# Sheet1.net
KiCad netlist of a schematic drawn in Altium Designer
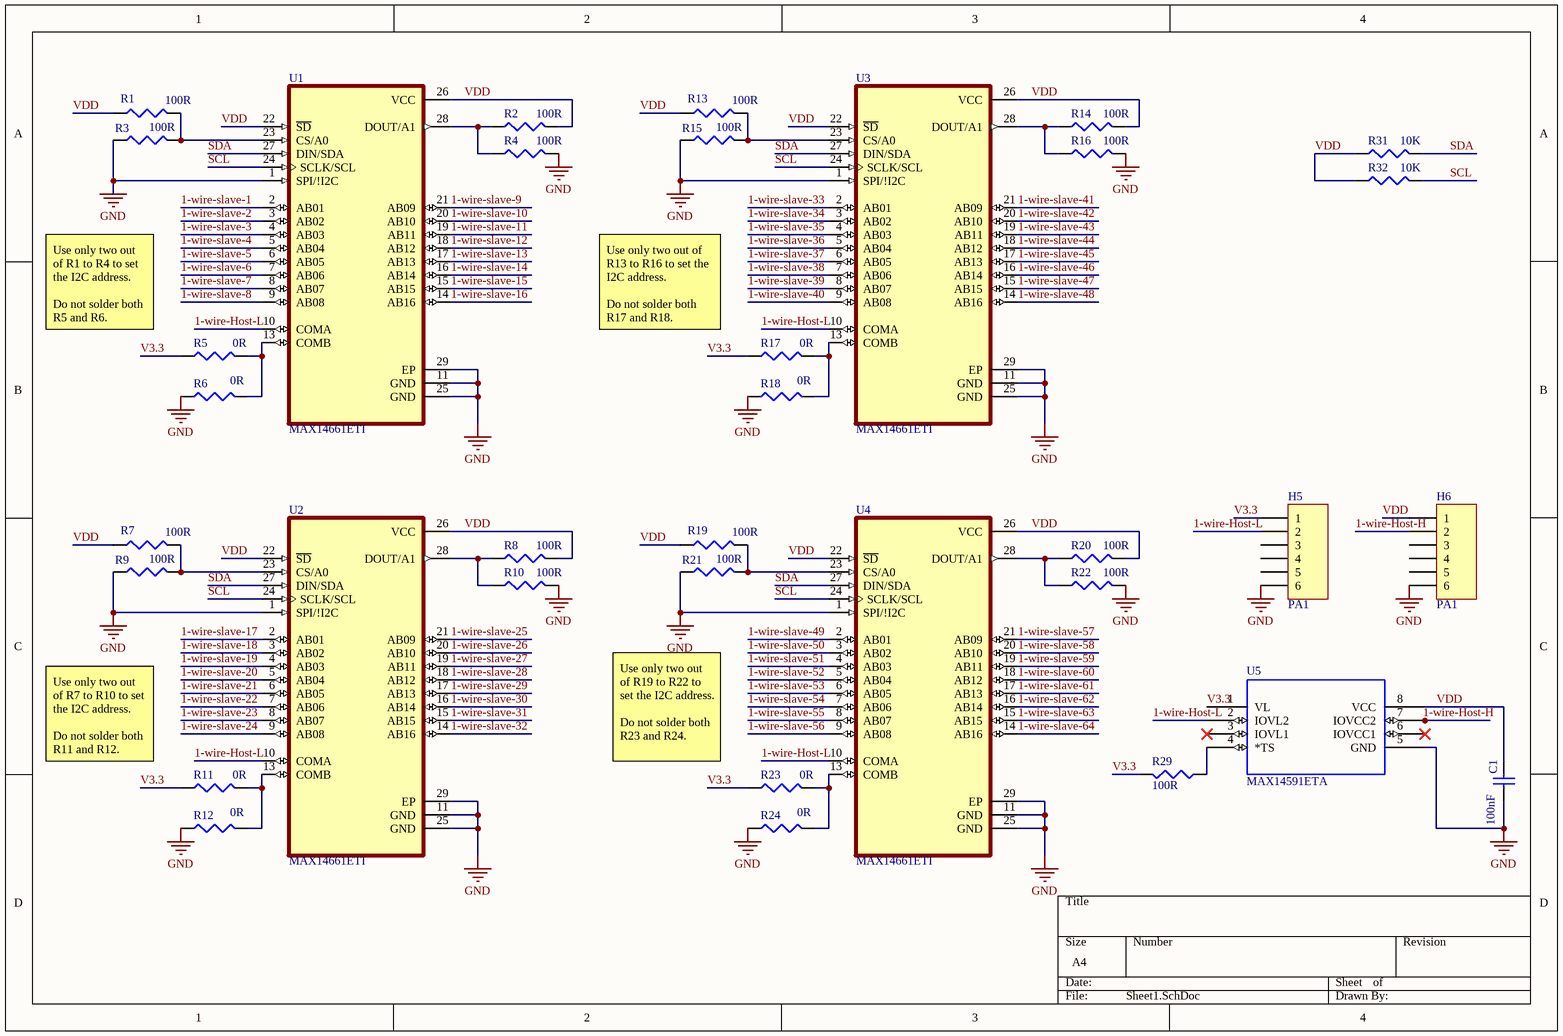
[diagram p0: Sheet1.SchDoc]

(export (version "E")
  (design (tool "Eeschema 10.0.6"))
  (components
    (comp (ref "C1")
      (value "100nF")
      (footprint "CAPC1608L")
      (description "Capacitor (Semiconductor SIM Model)")
      (fields (field (name "PUBLISHER") "Altium Limited"))
      (libsource (lib "Miscellaneous Devices") (part "Cap Semi"))
    )
    (comp (ref "H5")
      (value "PA1")
      (footprint "HDR1X6")
      (description "Header, 6-Pin")
      (fields (field (name "PUBLISHER") "Altium Limited"))
      (libsource (lib "Miscellaneous Connectors") (part "Header 6"))
    )
    (comp (ref "H6")
      (value "PA1")
      (footprint "HDR1X6")
      (description "Header, 6-Pin")
      (fields (field (name "PUBLISHER") "Altium Limited"))
      (libsource (lib "Miscellaneous Connectors") (part "Header 6"))
    )
    (comp (ref "R1")
      (value "100R")
      (footprint "J1-0603")
      (description "Resistor")
      (fields (field (name "PUBLISHER") "Altium Limited"))
      (libsource (lib "Miscellaneous Devices") (part "Res3"))
    )
    (comp (ref "R2")
      (value "100R")
      (footprint "J1-0603")
      (description "Resistor")
      (fields (field (name "PUBLISHER") "Altium Limited"))
      (libsource (lib "Miscellaneous Devices") (part "Res3"))
    )
    (comp (ref "R3")
      (value "100R")
      (footprint "J1-0603")
      (description "Resistor")
      (fields (field (name "PUBLISHER") "Altium Limited"))
      (libsource (lib "Miscellaneous Devices") (part "Res3"))
    )
    (comp (ref "R4")
      (value "100R")
      (footprint "J1-0603")
      (description "Resistor")
      (fields (field (name "PUBLISHER") "Altium Limited"))
      (libsource (lib "Miscellaneous Devices") (part "Res3"))
    )
    (comp (ref "R5")
      (value "0R")
      (footprint "J1-0603")
      (description "Resistor")
      (fields (field (name "PUBLISHER") "Altium Limited"))
      (libsource (lib "Miscellaneous Devices") (part "Res3"))
    )
    (comp (ref "R6")
      (value "0R")
      (footprint "J1-0603")
      (description "Resistor")
      (fields (field (name "PUBLISHER") "Altium Limited"))
      (libsource (lib "Miscellaneous Devices") (part "Res3"))
    )
    (comp (ref "R7")
      (value "100R")
      (footprint "J1-0603")
      (description "Resistor")
      (fields (field (name "PUBLISHER") "Altium Limited"))
      (libsource (lib "Miscellaneous Devices") (part "Res3"))
    )
    (comp (ref "R8")
      (value "100R")
      (footprint "J1-0603")
      (description "Resistor")
      (fields (field (name "PUBLISHER") "Altium Limited"))
      (libsource (lib "Miscellaneous Devices") (part "Res3"))
    )
    (comp (ref "R9")
      (value "100R")
      (footprint "J1-0603")
      (description "Resistor")
      (fields (field (name "PUBLISHER") "Altium Limited"))
      (libsource (lib "Miscellaneous Devices") (part "Res3"))
    )
    (comp (ref "R10")
      (value "100R")
      (footprint "J1-0603")
      (description "Resistor")
      (fields (field (name "PUBLISHER") "Altium Limited"))
      (libsource (lib "Miscellaneous Devices") (part "Res3"))
    )
    (comp (ref "R11")
      (value "0R")
      (footprint "J1-0603")
      (description "Resistor")
      (fields (field (name "PUBLISHER") "Altium Limited"))
      (libsource (lib "Miscellaneous Devices") (part "Res3"))
    )
    (comp (ref "R12")
      (value "0R")
      (footprint "J1-0603")
      (description "Resistor")
      (fields (field (name "PUBLISHER") "Altium Limited"))
      (libsource (lib "Miscellaneous Devices") (part "Res3"))
    )
    (comp (ref "R13")
      (value "100R")
      (footprint "J1-0603")
      (description "Resistor")
      (fields (field (name "PUBLISHER") "Altium Limited"))
      (libsource (lib "Miscellaneous Devices") (part "Res3"))
    )
    (comp (ref "R14")
      (value "100R")
      (footprint "J1-0603")
      (description "Resistor")
      (fields (field (name "PUBLISHER") "Altium Limited"))
      (libsource (lib "Miscellaneous Devices") (part "Res3"))
    )
    (comp (ref "R15")
      (value "100R")
      (footprint "J1-0603")
      (description "Resistor")
      (fields (field (name "PUBLISHER") "Altium Limited"))
      (libsource (lib "Miscellaneous Devices") (part "Res3"))
    )
    (comp (ref "R16")
      (value "100R")
      (footprint "J1-0603")
      (description "Resistor")
      (fields (field (name "PUBLISHER") "Altium Limited"))
      (libsource (lib "Miscellaneous Devices") (part "Res3"))
    )
    (comp (ref "R17")
      (value "0R")
      (footprint "J1-0603")
      (description "Resistor")
      (fields (field (name "PUBLISHER") "Altium Limited"))
      (libsource (lib "Miscellaneous Devices") (part "Res3"))
    )
    (comp (ref "R18")
      (value "0R")
      (footprint "J1-0603")
      (description "Resistor")
      (fields (field (name "PUBLISHER") "Altium Limited"))
      (libsource (lib "Miscellaneous Devices") (part "Res3"))
    )
    (comp (ref "R19")
      (value "100R")
      (footprint "J1-0603")
      (description "Resistor")
      (fields (field (name "PUBLISHER") "Altium Limited"))
      (libsource (lib "Miscellaneous Devices") (part "Res3"))
    )
    (comp (ref "R20")
      (value "100R")
      (footprint "J1-0603")
      (description "Resistor")
      (fields (field (name "PUBLISHER") "Altium Limited"))
      (libsource (lib "Miscellaneous Devices") (part "Res3"))
    )
    (comp (ref "R21")
      (value "100R")
      (footprint "J1-0603")
      (description "Resistor")
      (fields (field (name "PUBLISHER") "Altium Limited"))
      (libsource (lib "Miscellaneous Devices") (part "Res3"))
    )
    (comp (ref "R22")
      (value "100R")
      (footprint "J1-0603")
      (description "Resistor")
      (fields (field (name "PUBLISHER") "Altium Limited"))
      (libsource (lib "Miscellaneous Devices") (part "Res3"))
    )
    (comp (ref "R23")
      (value "0R")
      (footprint "J1-0603")
      (description "Resistor")
      (fields (field (name "PUBLISHER") "Altium Limited"))
      (libsource (lib "Miscellaneous Devices") (part "Res3"))
    )
    (comp (ref "R24")
      (value "0R")
      (footprint "J1-0603")
      (description "Resistor")
      (fields (field (name "PUBLISHER") "Altium Limited"))
      (libsource (lib "Miscellaneous Devices") (part "Res3"))
    )
    (comp (ref "R29")
      (value "100R")
      (footprint "J1-0603")
      (description "Resistor")
      (fields (field (name "PUBLISHER") "Altium Limited"))
      (libsource (lib "Miscellaneous Devices") (part "Res3"))
    )
    (comp (ref "R31")
      (value "10K")
      (footprint "J1-0603")
      (description "Resistor")
      (fields (field (name "PUBLISHER") "Altium Limited"))
      (libsource (lib "Miscellaneous Devices") (part "Res3"))
    )
    (comp (ref "R32")
      (value "10K")
      (footprint "J1-0603")
      (description "Resistor")
      (fields (field (name "PUBLISHER") "Altium Limited"))
      (libsource (lib "Miscellaneous Devices") (part "Res3"))
    )
    (comp (ref "U1")
      (value "MAX14661ETI")
      (footprint "MAX14661ETI+:QFN40P400X400X80-29N")
      (description "None")
      (fields (field (name "MF") "{'manufacturer': u'Maxim Integrated'}"))
      (libsource (lib "*") (part "MAX14661ETI"))
    )
    (comp (ref "U2")
      (value "MAX14661ETI")
      (footprint "MAX14661ETI+:QFN40P400X400X80-29N")
      (description "None")
      (fields (field (name "MF") "{'manufacturer': u'Maxim Integrated'}"))
      (libsource (lib "*") (part "MAX14661ETI"))
    )
    (comp (ref "U3")
      (value "MAX14661ETI")
      (footprint "MAX14661ETI+:QFN40P400X400X80-29N")
      (description "None")
      (fields (field (name "MF") "{'manufacturer': u'Maxim Integrated'}"))
      (libsource (lib "*") (part "MAX14661ETI"))
    )
    (comp (ref "U4")
      (value "MAX14661ETI")
      (footprint "MAX14661ETI+:QFN40P400X400X80-29N")
      (description "None")
      (fields (field (name "MF") "{'manufacturer': u'Maxim Integrated'}"))
      (libsource (lib "*") (part "MAX14661ETI"))
    )
    (comp (ref "U5")
      (value "MAX14591ETA")
      (footprint "MAX14591ETA+:21-0487A")
      (fields (field (name "MF") "{'manufacturer': u'Maxim Integrated'}"))
      (libsource (lib "MAX14591ETA+") (part "MAX14591ETA"))
    )
  )
  (nets
    (net (code "1") (name "/1-wire-Host-H") (class "Default")
      (node (ref "H6") (pin "2") (pinfunction "2_2") (pintype "passive"))
      (node (ref "U5") (pin "7") (pinfunction "IOVCC2_7") (pintype "bidirectional"))
    )
    (net (code "2") (name "/1-wire-Host-L") (class "Default")
      (node (ref "H5") (pin "2") (pinfunction "2_2") (pintype "passive"))
      (node (ref "U1") (pin "10") (pinfunction "COMA_10") (pintype "bidirectional"))
      (node (ref "U2") (pin "10") (pinfunction "COMA_10") (pintype "bidirectional"))
      (node (ref "U3") (pin "10") (pinfunction "COMA_10") (pintype "bidirectional"))
      (node (ref "U4") (pin "10") (pinfunction "COMA_10") (pintype "bidirectional"))
      (node (ref "U5") (pin "2") (pinfunction "IOVL2_2") (pintype "bidirectional"))
    )
    (net (code "3") (name "/1-wire-slave-1") (class "Default")
      (node (ref "U1") (pin "2") (pinfunction "AB01_2") (pintype "bidirectional"))
    )
    (net (code "4") (name "/1-wire-slave-2") (class "Default")
      (node (ref "U1") (pin "3") (pinfunction "AB02_3") (pintype "bidirectional"))
    )
    (net (code "5") (name "/1-wire-slave-3") (class "Default")
      (node (ref "U1") (pin "4") (pinfunction "AB03_4") (pintype "bidirectional"))
    )
    (net (code "6") (name "/1-wire-slave-4") (class "Default")
      (node (ref "U1") (pin "5") (pinfunction "AB04_5") (pintype "bidirectional"))
    )
    (net (code "7") (name "/1-wire-slave-5") (class "Default")
      (node (ref "U1") (pin "6") (pinfunction "AB05_6") (pintype "bidirectional"))
    )
    (net (code "8") (name "/1-wire-slave-6") (class "Default")
      (node (ref "U1") (pin "7") (pinfunction "AB06_7") (pintype "bidirectional"))
    )
    (net (code "9") (name "/1-wire-slave-7") (class "Default")
      (node (ref "U1") (pin "8") (pinfunction "AB07_8") (pintype "bidirectional"))
    )
    (net (code "10") (name "/1-wire-slave-8") (class "Default")
      (node (ref "U1") (pin "9") (pinfunction "AB08_9") (pintype "bidirectional"))
    )
    (net (code "11") (name "/1-wire-slave-9") (class "Default")
      (node (ref "U1") (pin "21") (pinfunction "AB09_21") (pintype "bidirectional"))
    )
    (net (code "12") (name "/1-wire-slave-10") (class "Default")
      (node (ref "U1") (pin "20") (pinfunction "AB10_20") (pintype "bidirectional"))
    )
    (net (code "13") (name "/1-wire-slave-11") (class "Default")
      (node (ref "U1") (pin "19") (pinfunction "AB11_19") (pintype "bidirectional"))
    )
    (net (code "14") (name "/1-wire-slave-12") (class "Default")
      (node (ref "U1") (pin "18") (pinfunction "AB12_18") (pintype "bidirectional"))
    )
    (net (code "15") (name "/1-wire-slave-13") (class "Default")
      (node (ref "U1") (pin "17") (pinfunction "AB13_17") (pintype "bidirectional"))
    )
    (net (code "16") (name "/1-wire-slave-14") (class "Default")
      (node (ref "U1") (pin "16") (pinfunction "AB14_16") (pintype "bidirectional"))
    )
    (net (code "17") (name "/1-wire-slave-15") (class "Default")
      (node (ref "U1") (pin "15") (pinfunction "AB15_15") (pintype "bidirectional"))
    )
    (net (code "18") (name "/1-wire-slave-16") (class "Default")
      (node (ref "U1") (pin "14") (pinfunction "AB16_14") (pintype "bidirectional"))
    )
    (net (code "19") (name "/1-wire-slave-17") (class "Default")
      (node (ref "U2") (pin "2") (pinfunction "AB01_2") (pintype "bidirectional"))
    )
    (net (code "20") (name "/1-wire-slave-18") (class "Default")
      (node (ref "U2") (pin "3") (pinfunction "AB02_3") (pintype "bidirectional"))
    )
    (net (code "21") (name "/1-wire-slave-19") (class "Default")
      (node (ref "U2") (pin "4") (pinfunction "AB03_4") (pintype "bidirectional"))
    )
    (net (code "22") (name "/1-wire-slave-20") (class "Default")
      (node (ref "U2") (pin "5") (pinfunction "AB04_5") (pintype "bidirectional"))
    )
    (net (code "23") (name "/1-wire-slave-21") (class "Default")
      (node (ref "U2") (pin "6") (pinfunction "AB05_6") (pintype "bidirectional"))
    )
    (net (code "24") (name "/1-wire-slave-22") (class "Default")
      (node (ref "U2") (pin "7") (pinfunction "AB06_7") (pintype "bidirectional"))
    )
    (net (code "25") (name "/1-wire-slave-23") (class "Default")
      (node (ref "U2") (pin "8") (pinfunction "AB07_8") (pintype "bidirectional"))
    )
    (net (code "26") (name "/1-wire-slave-24") (class "Default")
      (node (ref "U2") (pin "9") (pinfunction "AB08_9") (pintype "bidirectional"))
    )
    (net (code "27") (name "/1-wire-slave-25") (class "Default")
      (node (ref "U2") (pin "21") (pinfunction "AB09_21") (pintype "bidirectional"))
    )
    (net (code "28") (name "/1-wire-slave-26") (class "Default")
      (node (ref "U2") (pin "20") (pinfunction "AB10_20") (pintype "bidirectional"))
    )
    (net (code "29") (name "/1-wire-slave-27") (class "Default")
      (node (ref "U2") (pin "19") (pinfunction "AB11_19") (pintype "bidirectional"))
    )
    (net (code "30") (name "/1-wire-slave-28") (class "Default")
      (node (ref "U2") (pin "18") (pinfunction "AB12_18") (pintype "bidirectional"))
    )
    (net (code "31") (name "/1-wire-slave-29") (class "Default")
      (node (ref "U2") (pin "17") (pinfunction "AB13_17") (pintype "bidirectional"))
    )
    (net (code "32") (name "/1-wire-slave-30") (class "Default")
      (node (ref "U2") (pin "16") (pinfunction "AB14_16") (pintype "bidirectional"))
    )
    (net (code "33") (name "/1-wire-slave-31") (class "Default")
      (node (ref "U2") (pin "15") (pinfunction "AB15_15") (pintype "bidirectional"))
    )
    (net (code "34") (name "/1-wire-slave-32") (class "Default")
      (node (ref "U2") (pin "14") (pinfunction "AB16_14") (pintype "bidirectional"))
    )
    (net (code "35") (name "/1-wire-slave-33") (class "Default")
      (node (ref "U3") (pin "2") (pinfunction "AB01_2") (pintype "bidirectional"))
    )
    (net (code "36") (name "/1-wire-slave-34") (class "Default")
      (node (ref "U3") (pin "3") (pinfunction "AB02_3") (pintype "bidirectional"))
    )
    (net (code "37") (name "/1-wire-slave-35") (class "Default")
      (node (ref "U3") (pin "4") (pinfunction "AB03_4") (pintype "bidirectional"))
    )
    (net (code "38") (name "/1-wire-slave-36") (class "Default")
      (node (ref "U3") (pin "5") (pinfunction "AB04_5") (pintype "bidirectional"))
    )
    (net (code "39") (name "/1-wire-slave-37") (class "Default")
      (node (ref "U3") (pin "6") (pinfunction "AB05_6") (pintype "bidirectional"))
    )
    (net (code "40") (name "/1-wire-slave-38") (class "Default")
      (node (ref "U3") (pin "7") (pinfunction "AB06_7") (pintype "bidirectional"))
    )
    (net (code "41") (name "/1-wire-slave-39") (class "Default")
      (node (ref "U3") (pin "8") (pinfunction "AB07_8") (pintype "bidirectional"))
    )
    (net (code "42") (name "/1-wire-slave-40") (class "Default")
      (node (ref "U3") (pin "9") (pinfunction "AB08_9") (pintype "bidirectional"))
    )
    (net (code "43") (name "/1-wire-slave-41") (class "Default")
      (node (ref "U3") (pin "21") (pinfunction "AB09_21") (pintype "bidirectional"))
    )
    (net (code "44") (name "/1-wire-slave-42") (class "Default")
      (node (ref "U3") (pin "20") (pinfunction "AB10_20") (pintype "bidirectional"))
    )
    (net (code "45") (name "/1-wire-slave-43") (class "Default")
      (node (ref "U3") (pin "19") (pinfunction "AB11_19") (pintype "bidirectional"))
    )
    (net (code "46") (name "/1-wire-slave-44") (class "Default")
      (node (ref "U3") (pin "18") (pinfunction "AB12_18") (pintype "bidirectional"))
    )
    (net (code "47") (name "/1-wire-slave-45") (class "Default")
      (node (ref "U3") (pin "17") (pinfunction "AB13_17") (pintype "bidirectional"))
    )
    (net (code "48") (name "/1-wire-slave-46") (class "Default")
      (node (ref "U3") (pin "16") (pinfunction "AB14_16") (pintype "bidirectional"))
    )
    (net (code "49") (name "/1-wire-slave-47") (class "Default")
      (node (ref "U3") (pin "15") (pinfunction "AB15_15") (pintype "bidirectional"))
    )
    (net (code "50") (name "/1-wire-slave-48") (class "Default")
      (node (ref "U3") (pin "14") (pinfunction "AB16_14") (pintype "bidirectional"))
    )
    (net (code "51") (name "/1-wire-slave-49") (class "Default")
      (node (ref "U4") (pin "2") (pinfunction "AB01_2") (pintype "bidirectional"))
    )
    (net (code "52") (name "/1-wire-slave-50") (class "Default")
      (node (ref "U4") (pin "3") (pinfunction "AB02_3") (pintype "bidirectional"))
    )
    (net (code "53") (name "/1-wire-slave-51") (class "Default")
      (node (ref "U4") (pin "4") (pinfunction "AB03_4") (pintype "bidirectional"))
    )
    (net (code "54") (name "/1-wire-slave-52") (class "Default")
      (node (ref "U4") (pin "5") (pinfunction "AB04_5") (pintype "bidirectional"))
    )
    (net (code "55") (name "/1-wire-slave-53") (class "Default")
      (node (ref "U4") (pin "6") (pinfunction "AB05_6") (pintype "bidirectional"))
    )
    (net (code "56") (name "/1-wire-slave-54") (class "Default")
      (node (ref "U4") (pin "7") (pinfunction "AB06_7") (pintype "bidirectional"))
    )
    (net (code "57") (name "/1-wire-slave-55") (class "Default")
      (node (ref "U4") (pin "8") (pinfunction "AB07_8") (pintype "bidirectional"))
    )
    (net (code "58") (name "/1-wire-slave-56") (class "Default")
      (node (ref "U4") (pin "9") (pinfunction "AB08_9") (pintype "bidirectional"))
    )
    (net (code "59") (name "/1-wire-slave-57") (class "Default")
      (node (ref "U4") (pin "21") (pinfunction "AB09_21") (pintype "bidirectional"))
    )
    (net (code "60") (name "/1-wire-slave-58") (class "Default")
      (node (ref "U4") (pin "20") (pinfunction "AB10_20") (pintype "bidirectional"))
    )
    (net (code "61") (name "/1-wire-slave-59") (class "Default")
      (node (ref "U4") (pin "19") (pinfunction "AB11_19") (pintype "bidirectional"))
    )
    (net (code "62") (name "/1-wire-slave-60") (class "Default")
      (node (ref "U4") (pin "18") (pinfunction "AB12_18") (pintype "bidirectional"))
    )
    (net (code "63") (name "/1-wire-slave-61") (class "Default")
      (node (ref "U4") (pin "17") (pinfunction "AB13_17") (pintype "bidirectional"))
    )
    (net (code "64") (name "/1-wire-slave-62") (class "Default")
      (node (ref "U4") (pin "16") (pinfunction "AB14_16") (pintype "bidirectional"))
    )
    (net (code "65") (name "/1-wire-slave-63") (class "Default")
      (node (ref "U4") (pin "15") (pinfunction "AB15_15") (pintype "bidirectional"))
    )
    (net (code "66") (name "/1-wire-slave-64") (class "Default")
      (node (ref "U4") (pin "14") (pinfunction "AB16_14") (pintype "bidirectional"))
    )
    (net (code "67") (name "/SCL") (class "Default")
      (node (ref "R32") (pin "1") (pinfunction "1_1") (pintype "passive"))
      (node (ref "U1") (pin "24") (pinfunction "SCLK/SCL_24") (pintype "input"))
      (node (ref "U2") (pin "24") (pinfunction "SCLK/SCL_24") (pintype "input"))
      (node (ref "U3") (pin "24") (pinfunction "SCLK/SCL_24") (pintype "input"))
      (node (ref "U4") (pin "24") (pinfunction "SCLK/SCL_24") (pintype "input"))
    )
    (net (code "68") (name "/SDA") (class "Default")
      (node (ref "R31") (pin "1") (pinfunction "1_1") (pintype "passive"))
      (node (ref "U1") (pin "27") (pinfunction "DIN/SDA_27") (pintype "input"))
      (node (ref "U2") (pin "27") (pinfunction "DIN/SDA_27") (pintype "input"))
      (node (ref "U3") (pin "27") (pinfunction "DIN/SDA_27") (pintype "input"))
      (node (ref "U4") (pin "27") (pinfunction "DIN/SDA_27") (pintype "input"))
    )
    (net (code "69") (name "/V3.3") (class "Default")
      (node (ref "H5") (pin "1") (pinfunction "1_1") (pintype "passive"))
      (node (ref "R11") (pin "1") (pinfunction "1_1") (pintype "passive"))
      (node (ref "R17") (pin "1") (pinfunction "1_1") (pintype "passive"))
      (node (ref "R23") (pin "1") (pinfunction "1_1") (pintype "passive"))
      (node (ref "R29") (pin "1") (pinfunction "1_1") (pintype "passive"))
      (node (ref "R5") (pin "1") (pinfunction "1_1") (pintype "passive"))
      (node (ref "U5") (pin "1") (pinfunction "VL_1") (pintype "power_in"))
    )
    (net (code "70") (name "/VDD") (class "Default")
      (node (ref "C1") (pin "1") (pinfunction "1_1") (pintype "passive"))
      (node (ref "H6") (pin "1") (pinfunction "1_1") (pintype "passive"))
      (node (ref "R1") (pin "1") (pinfunction "1_1") (pintype "passive"))
      (node (ref "R13") (pin "1") (pinfunction "1_1") (pintype "passive"))
      (node (ref "R14") (pin "1") (pinfunction "1_1") (pintype "passive"))
      (node (ref "R19") (pin "1") (pinfunction "1_1") (pintype "passive"))
      (node (ref "R2") (pin "1") (pinfunction "1_1") (pintype "passive"))
      (node (ref "R20") (pin "1") (pinfunction "1_1") (pintype "passive"))
      (node (ref "R31") (pin "2") (pinfunction "2_2") (pintype "passive"))
      (node (ref "R32") (pin "2") (pinfunction "2_2") (pintype "passive"))
      (node (ref "R7") (pin "1") (pinfunction "1_1") (pintype "passive"))
      (node (ref "R8") (pin "1") (pinfunction "1_1") (pintype "passive"))
      (node (ref "U1") (pin "22") (pinfunction "~{SD}_22") (pintype "input"))
      (node (ref "U1") (pin "26") (pinfunction "VCC_26") (pintype "power_in"))
      (node (ref "U2") (pin "22") (pinfunction "~{SD}_22") (pintype "input"))
      (node (ref "U2") (pin "26") (pinfunction "VCC_26") (pintype "power_in"))
      (node (ref "U3") (pin "22") (pinfunction "~{SD}_22") (pintype "input"))
      (node (ref "U3") (pin "26") (pinfunction "VCC_26") (pintype "power_in"))
      (node (ref "U4") (pin "22") (pinfunction "~{SD}_22") (pintype "input"))
      (node (ref "U4") (pin "26") (pinfunction "VCC_26") (pintype "power_in"))
      (node (ref "U5") (pin "8") (pinfunction "VCC_8") (pintype "power_in"))
    )
    (net (code "71") (name "GND") (class "Default")
      (node (ref "C1") (pin "2") (pinfunction "2_2") (pintype "passive"))
      (node (ref "H5") (pin "6") (pinfunction "6_6") (pintype "passive"))
      (node (ref "H6") (pin "6") (pinfunction "6_6") (pintype "passive"))
      (node (ref "R10") (pin "1") (pinfunction "1_1") (pintype "passive"))
      (node (ref "R12") (pin "1") (pinfunction "1_1") (pintype "passive"))
      (node (ref "R15") (pin "1") (pinfunction "1_1") (pintype "passive"))
      (node (ref "R16") (pin "1") (pinfunction "1_1") (pintype "passive"))
      (node (ref "R18") (pin "1") (pinfunction "1_1") (pintype "passive"))
      (node (ref "R21") (pin "1") (pinfunction "1_1") (pintype "passive"))
      (node (ref "R22") (pin "1") (pinfunction "1_1") (pintype "passive"))
      (node (ref "R24") (pin "1") (pinfunction "1_1") (pintype "passive"))
      (node (ref "R3") (pin "1") (pinfunction "1_1") (pintype "passive"))
      (node (ref "R4") (pin "1") (pinfunction "1_1") (pintype "passive"))
      (node (ref "R6") (pin "1") (pinfunction "1_1") (pintype "passive"))
      (node (ref "R9") (pin "1") (pinfunction "1_1") (pintype "passive"))
      (node (ref "U1") (pin "1") (pinfunction "SPI/!I2C_1") (pintype "input"))
      (node (ref "U1") (pin "11") (pinfunction "GND_11") (pintype "power_in"))
      (node (ref "U1") (pin "25") (pinfunction "GND_25") (pintype "power_in"))
      (node (ref "U1") (pin "29") (pinfunction "EP_29") (pintype "power_in"))
      (node (ref "U2") (pin "1") (pinfunction "SPI/!I2C_1") (pintype "input"))
      (node (ref "U2") (pin "11") (pinfunction "GND_11") (pintype "power_in"))
      (node (ref "U2") (pin "25") (pinfunction "GND_25") (pintype "power_in"))
      (node (ref "U2") (pin "29") (pinfunction "EP_29") (pintype "power_in"))
      (node (ref "U3") (pin "1") (pinfunction "SPI/!I2C_1") (pintype "input"))
      (node (ref "U3") (pin "11") (pinfunction "GND_11") (pintype "power_in"))
      (node (ref "U3") (pin "25") (pinfunction "GND_25") (pintype "power_in"))
      (node (ref "U3") (pin "29") (pinfunction "EP_29") (pintype "power_in"))
      (node (ref "U4") (pin "1") (pinfunction "SPI/!I2C_1") (pintype "input"))
      (node (ref "U4") (pin "11") (pinfunction "GND_11") (pintype "power_in"))
      (node (ref "U4") (pin "25") (pinfunction "GND_25") (pintype "power_in"))
      (node (ref "U4") (pin "29") (pinfunction "EP_29") (pintype "power_in"))
      (node (ref "U5") (pin "5") (pinfunction "GND_5") (pintype "power_in"))
    )
    (net (code "72") (name "Net-(U1-COMB)") (class "Default")
      (node (ref "R5") (pin "2") (pinfunction "2_2") (pintype "passive"))
      (node (ref "R6") (pin "2") (pinfunction "2_2") (pintype "passive"))
      (node (ref "U1") (pin "13") (pinfunction "COMB_13") (pintype "bidirectional"))
    )
    (net (code "73") (name "Net-(U1-CS{slash}A0)") (class "Default")
      (node (ref "R1") (pin "2") (pinfunction "2_2") (pintype "passive"))
      (node (ref "R3") (pin "2") (pinfunction "2_2") (pintype "passive"))
      (node (ref "U1") (pin "23") (pinfunction "CS/A0_23") (pintype "input"))
    )
    (net (code "74") (name "Net-(U1-DOUT{slash}A1)") (class "Default")
      (node (ref "R2") (pin "2") (pinfunction "2_2") (pintype "passive"))
      (node (ref "R4") (pin "2") (pinfunction "2_2") (pintype "passive"))
      (node (ref "U1") (pin "28") (pinfunction "DOUT/A1_28") (pintype "output"))
    )
    (net (code "75") (name "Net-(U2-COMB)") (class "Default")
      (node (ref "R11") (pin "2") (pinfunction "2_2") (pintype "passive"))
      (node (ref "R12") (pin "2") (pinfunction "2_2") (pintype "passive"))
      (node (ref "U2") (pin "13") (pinfunction "COMB_13") (pintype "bidirectional"))
    )
    (net (code "76") (name "Net-(U2-CS{slash}A0)") (class "Default")
      (node (ref "R7") (pin "2") (pinfunction "2_2") (pintype "passive"))
      (node (ref "R9") (pin "2") (pinfunction "2_2") (pintype "passive"))
      (node (ref "U2") (pin "23") (pinfunction "CS/A0_23") (pintype "input"))
    )
    (net (code "77") (name "Net-(U2-DOUT{slash}A1)") (class "Default")
      (node (ref "R10") (pin "2") (pinfunction "2_2") (pintype "passive"))
      (node (ref "R8") (pin "2") (pinfunction "2_2") (pintype "passive"))
      (node (ref "U2") (pin "28") (pinfunction "DOUT/A1_28") (pintype "output"))
    )
    (net (code "78") (name "Net-(U3-COMB)") (class "Default")
      (node (ref "R17") (pin "2") (pinfunction "2_2") (pintype "passive"))
      (node (ref "R18") (pin "2") (pinfunction "2_2") (pintype "passive"))
      (node (ref "U3") (pin "13") (pinfunction "COMB_13") (pintype "bidirectional"))
    )
    (net (code "79") (name "Net-(U3-CS{slash}A0)") (class "Default")
      (node (ref "R13") (pin "2") (pinfunction "2_2") (pintype "passive"))
      (node (ref "R15") (pin "2") (pinfunction "2_2") (pintype "passive"))
      (node (ref "U3") (pin "23") (pinfunction "CS/A0_23") (pintype "input"))
    )
    (net (code "80") (name "Net-(U3-DOUT{slash}A1)") (class "Default")
      (node (ref "R14") (pin "2") (pinfunction "2_2") (pintype "passive"))
      (node (ref "R16") (pin "2") (pinfunction "2_2") (pintype "passive"))
      (node (ref "U3") (pin "28") (pinfunction "DOUT/A1_28") (pintype "output"))
    )
    (net (code "81") (name "Net-(U4-COMB)") (class "Default")
      (node (ref "R23") (pin "2") (pinfunction "2_2") (pintype "passive"))
      (node (ref "R24") (pin "2") (pinfunction "2_2") (pintype "passive"))
      (node (ref "U4") (pin "13") (pinfunction "COMB_13") (pintype "bidirectional"))
    )
    (net (code "82") (name "Net-(U4-CS{slash}A0)") (class "Default")
      (node (ref "R19") (pin "2") (pinfunction "2_2") (pintype "passive"))
      (node (ref "R21") (pin "2") (pinfunction "2_2") (pintype "passive"))
      (node (ref "U4") (pin "23") (pinfunction "CS/A0_23") (pintype "input"))
    )
    (net (code "83") (name "Net-(U4-DOUT{slash}A1)") (class "Default")
      (node (ref "R20") (pin "2") (pinfunction "2_2") (pintype "passive"))
      (node (ref "R22") (pin "2") (pinfunction "2_2") (pintype "passive"))
      (node (ref "U4") (pin "28") (pinfunction "DOUT/A1_28") (pintype "output"))
    )
    (net (code "84") (name "Net-(U5-*TS)") (class "Default")
      (node (ref "R29") (pin "2") (pinfunction "2_2") (pintype "passive"))
      (node (ref "U5") (pin "4") (pinfunction "*TS_4") (pintype "bidirectional"))
    )
    (net (code "85") (name "unconnected-(H5-Pad3)") (class "Default")
      (node (ref "H5") (pin "3") (pinfunction "3_3") (pintype "passive"))
    )
    (net (code "86") (name "unconnected-(H5-Pad4)") (class "Default")
      (node (ref "H5") (pin "4") (pinfunction "4_4") (pintype "passive"))
    )
    (net (code "87") (name "unconnected-(H5-Pad5)") (class "Default")
      (node (ref "H5") (pin "5") (pinfunction "5_5") (pintype "passive"))
    )
    (net (code "88") (name "unconnected-(H6-Pad3)") (class "Default")
      (node (ref "H6") (pin "3") (pinfunction "3_3") (pintype "passive"))
    )
    (net (code "89") (name "unconnected-(H6-Pad4)") (class "Default")
      (node (ref "H6") (pin "4") (pinfunction "4_4") (pintype "passive"))
    )
    (net (code "90") (name "unconnected-(H6-Pad5)") (class "Default")
      (node (ref "H6") (pin "5") (pinfunction "5_5") (pintype "passive"))
    )
    (net (code "91") (name "unconnected-(U5-IOVCC1-Pad6)") (class "Default")
      (node (ref "U5") (pin "6") (pinfunction "IOVCC1_6") (pintype "bidirectional+no_connect"))
    )
    (net (code "92") (name "unconnected-(U5-IOVL1-Pad3)") (class "Default")
      (node (ref "U5") (pin "3") (pinfunction "IOVL1_3") (pintype "bidirectional+no_connect"))
    )
  )
)
